# SparkFun_ESP8266_Thing.net
KiCad netlist of a schematic drawn in EAGLE
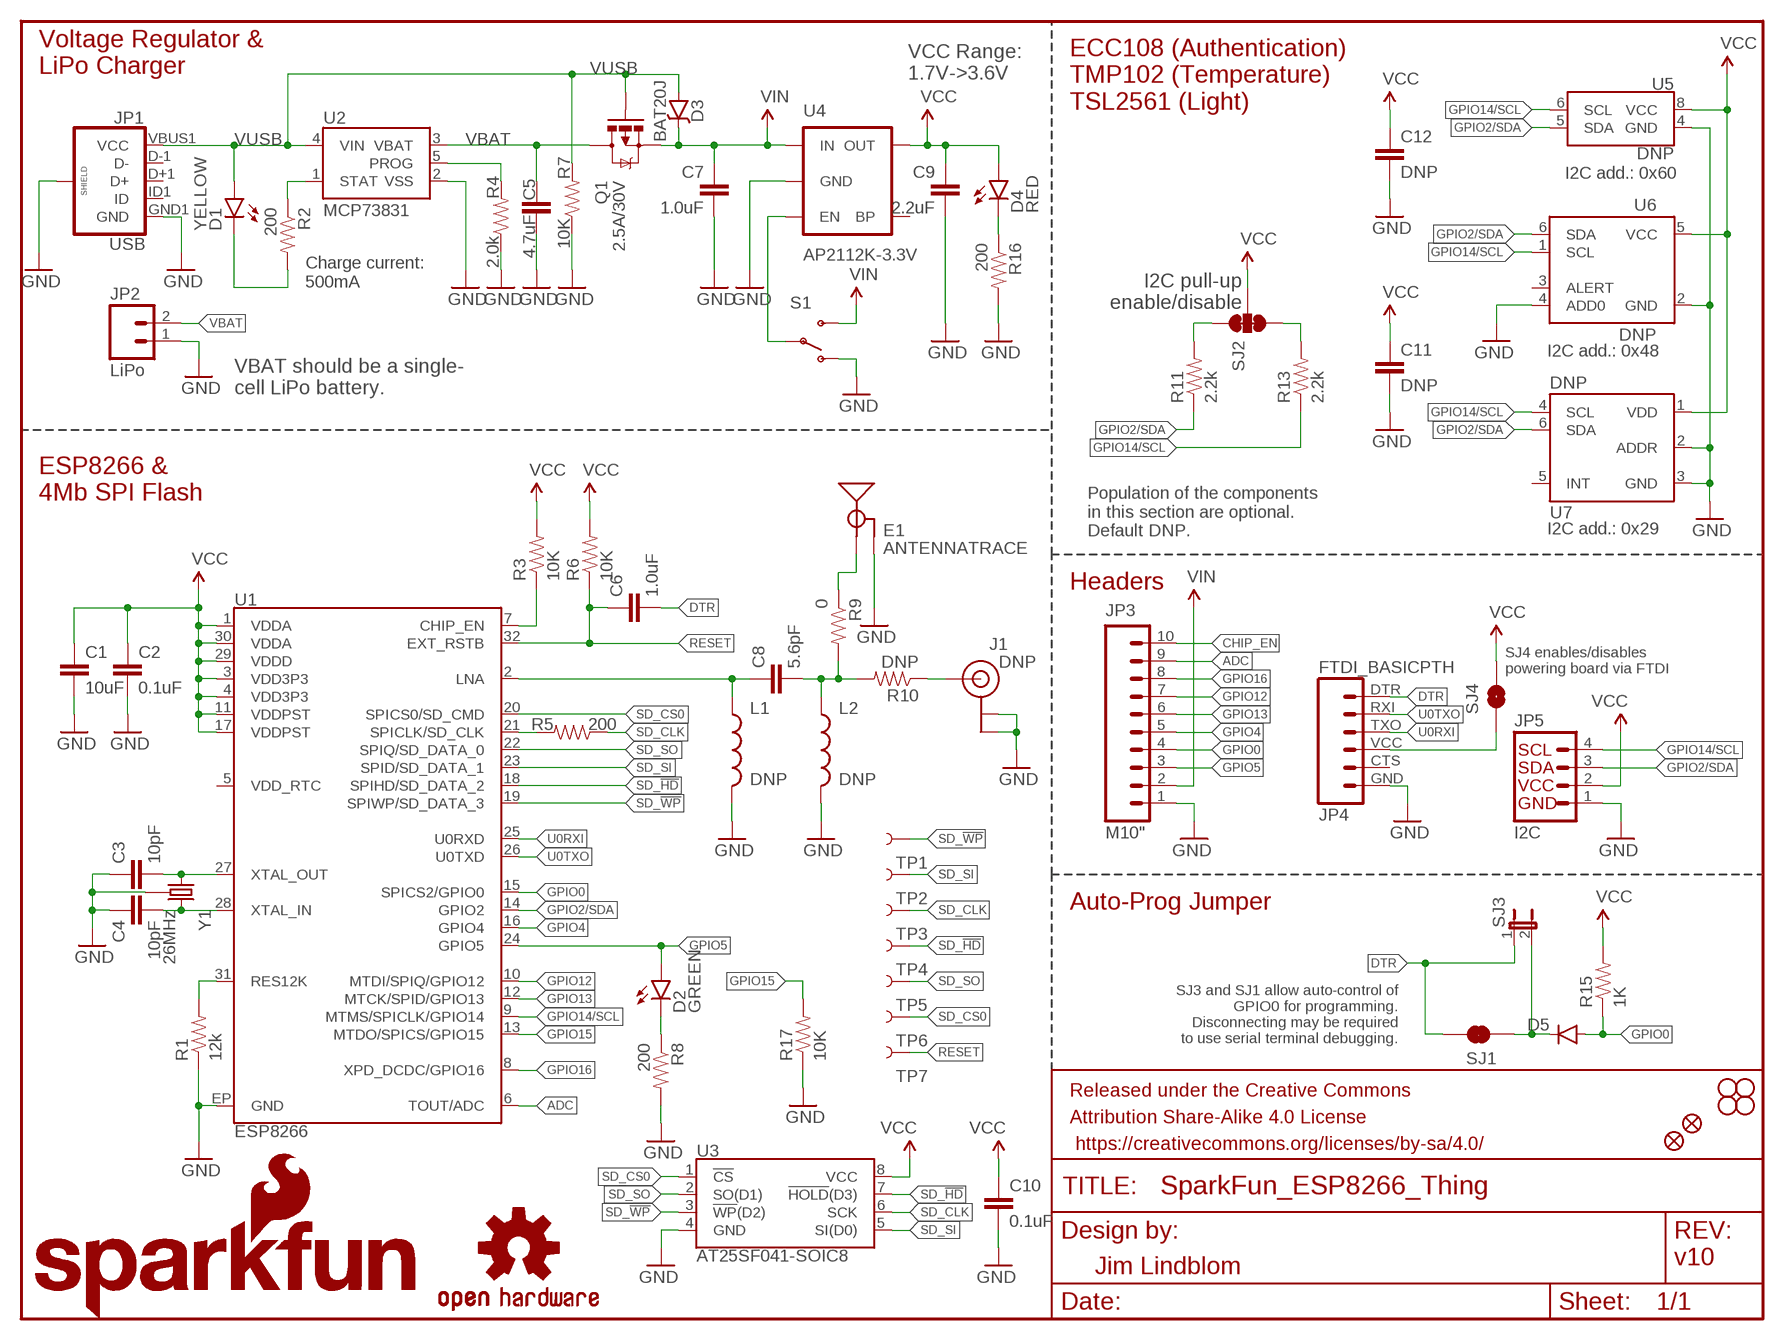
[diagram p0: schematic, sheet 1]

(export (version "E")
  (design (tool "Eeschema 10.0.6"))
  (components
    (comp (ref "C1")
      (value "10uF")
      (footprint "eagle-import:0603-CAP")
      (libsource (lib "eagle-import") (part "10UF-6.3V-20%(0603)"))
    )
    (comp (ref "C2")
      (value "0.1uF")
      (footprint "eagle-import:0603-CAP")
      (libsource (lib "eagle-import") (part "0.1UF-25V(+80/-20%)(0603)"))
    )
    (comp (ref "C3")
      (value "10pF")
      (footprint "eagle-import:0603-CAP")
      (libsource (lib "eagle-import") (part "10PF-50V-5%(0603)"))
    )
    (comp (ref "C4")
      (value "10pF")
      (footprint "eagle-import:0603-CAP")
      (libsource (lib "eagle-import") (part "10PF-50V-5%(0603)"))
    )
    (comp (ref "C5")
      (value "4.7uF")
      (footprint "eagle-import:0603-CAP")
      (libsource (lib "eagle-import") (part "4.7UF-6.3V-10%(0603)0603"))
    )
    (comp (ref "C6")
      (value "1.0uF")
      (footprint "eagle-import:0603-CAP")
      (libsource (lib "eagle-import") (part "1.0UF-16V-10%(0603)"))
    )
    (comp (ref "C7")
      (value "1.0uF")
      (footprint "eagle-import:0805")
      (libsource (lib "eagle-import") (part "1.0UF-25V-+80/-20(0805)"))
    )
    (comp (ref "C8")
      (value "5.6pF")
      (footprint "eagle-import:0603-CAP")
      (libsource (lib "eagle-import") (part "CAP0603-CAP"))
    )
    (comp (ref "C9")
      (value "2.2uF")
      (footprint "eagle-import:0603-CAP")
      (libsource (lib "eagle-import") (part "2.2UF-10V-20%(0603)"))
    )
    (comp (ref "C10")
      (value "0.1uF")
      (footprint "eagle-import:0603-CAP")
      (libsource (lib "eagle-import") (part "0.1UF-25V(+80/-20%)(0603)"))
    )
    (comp (ref "C11")
      (value "DNP")
      (footprint "eagle-import:0603-CAP")
      (libsource (lib "eagle-import") (part "0.1UF-25V(+80/-20%)(0603)"))
    )
    (comp (ref "C12")
      (value "DNP")
      (footprint "eagle-import:0603-CAP")
      (libsource (lib "eagle-import") (part "0.1UF-25V(+80/-20%)(0603)"))
    )
    (comp (ref "D1")
      (value "YELLOW")
      (footprint "eagle-import:LED-0603")
      (libsource (lib "eagle-import") (part "LED-YELLOW0603"))
    )
    (comp (ref "D2")
      (value "GREEN")
      (footprint "eagle-import:LED-0603")
      (libsource (lib "eagle-import") (part "LED-GREEN0603"))
    )
    (comp (ref "D3")
      (value "BAT20J")
      (footprint "eagle-import:SOD-323")
      (libsource (lib "eagle-import") (part "DIODE-SCHOTTKY-BAT20J"))
    )
    (comp (ref "D4")
      (value "RED")
      (footprint "eagle-import:LED-0603")
      (libsource (lib "eagle-import") (part "LED-RED0603"))
    )
    (comp (ref "D5")
      (value "DIODEBAS16")
      (footprint "eagle-import:SOD-323")
      (libsource (lib "eagle-import") (part "DIODEBAS16"))
    )
    (comp (ref "E1")
      (value "ANTENNATRACE")
      (footprint "eagle-import:TRACE_ANTENNA_2.4GHZ_25.7MM")
      (libsource (lib "eagle-import") (part "ANTENNATRACE"))
    )
    (comp (ref "FID1")
      (value "FIDUCIAL1X2")
      (footprint "eagle-import:FIDUCIAL-1X2")
      (libsource (lib "eagle-import") (part "FIDUCIAL1X2"))
    )
    (comp (ref "FID2")
      (value "FIDUCIAL1X2")
      (footprint "eagle-import:FIDUCIAL-1X2")
      (libsource (lib "eagle-import") (part "FIDUCIAL1X2"))
    )
    (comp (ref "FRAME1")
      (value "FRAME-LETTER")
      (footprint "eagle-import:CREATIVE_COMMONS")
      (libsource (lib "eagle-import") (part "FRAME-LETTER"))
    )
    (comp (ref "J1")
      (value "DNP")
      (footprint "eagle-import:U.FL")
      (libsource (lib "eagle-import") (part "U.FL"))
    )
    (comp (ref "JP1")
      (value "USB")
      (footprint "eagle-import:USB-B-MICRO-SMD_V03")
      (libsource (lib "eagle-import") (part "USB_MICROB_PLUGCONN-11752"))
    )
    (comp (ref "JP2")
      (value "LiPo")
      (footprint "eagle-import:JST-2-PTH")
      (libsource (lib "eagle-import") (part "M02JST-PTH-2"))
    )
    (comp (ref "JP3")
      (value "M10\"")
      (footprint "eagle-import:1X10")
      (libsource (lib "eagle-import") (part "M10{dblquote}"))
    )
    (comp (ref "JP4")
      (value "FTDI_BASICPTH")
      (footprint "eagle-import:FTDI_BASIC")
      (libsource (lib "eagle-import") (part "FTDI_BASICPTH"))
    )
    (comp (ref "JP5")
      (value "I2C")
      (footprint "eagle-import:1X04")
      (libsource (lib "eagle-import") (part "I2C_STANDARD"))
    )
    (comp (ref "L1")
      (value "DNP")
      (footprint "eagle-import:0603")
      (libsource (lib "eagle-import") (part "INDUCTOR0603"))
    )
    (comp (ref "L2")
      (value "DNP")
      (footprint "eagle-import:0603")
      (libsource (lib "eagle-import") (part "INDUCTOR0603"))
    )
    (comp (ref "LOGO1")
      (value "SFE_LOGO_NAME.2_INCH")
      (footprint "eagle-import:SFE_LOGO_NAME_.2")
      (libsource (lib "eagle-import") (part "SFE_LOGO_NAME.2_INCH"))
    )
    (comp (ref "LOGO3")
      (value "SFE_LOGO_FLAME.1_INCH")
      (footprint "eagle-import:SFE_LOGO_FLAME_.1")
      (libsource (lib "eagle-import") (part "SFE_LOGO_FLAME.1_INCH"))
    )
    (comp (ref "LOGO4")
      (value "OSHW-LOGOS")
      (footprint "eagle-import:OSHW-LOGO-S")
      (libsource (lib "eagle-import") (part "OSHW-LOGOS"))
    )
    (comp (ref "Q1")
      (value "2.5A/30V")
      (footprint "eagle-import:SOT23-3")
      (libsource (lib "eagle-import") (part "MOSFET-PCHANNELDMG2307L"))
    )
    (comp (ref "R1")
      (value "12k")
      (footprint "eagle-import:0603-RES")
      (libsource (lib "eagle-import") (part "12KOHM-1/10W-1%(0603)"))
    )
    (comp (ref "R2")
      (value "200")
      (footprint "eagle-import:0603-RES")
      (libsource (lib "eagle-import") (part "200OHM1/10W1%(0603)"))
    )
    (comp (ref "R3")
      (value "10K")
      (footprint "eagle-import:0603-RES")
      (libsource (lib "eagle-import") (part "10KOHM1/10W1%(0603)0603"))
    )
    (comp (ref "R4")
      (value "2.0k")
      (footprint "eagle-import:0603-RES")
      (libsource (lib "eagle-import") (part "2.0KOHM1/10W5%(0603)"))
    )
    (comp (ref "R5")
      (value "200")
      (footprint "eagle-import:0603-RES")
      (libsource (lib "eagle-import") (part "200OHM1/10W1%(0603)"))
    )
    (comp (ref "R6")
      (value "10K")
      (footprint "eagle-import:0603-RES")
      (libsource (lib "eagle-import") (part "10KOHM1/10W1%(0603)0603"))
    )
    (comp (ref "R7")
      (value "10K")
      (footprint "eagle-import:0603-RES")
      (libsource (lib "eagle-import") (part "10KOHM1/10W1%(0603)0603"))
    )
    (comp (ref "R8")
      (value "200")
      (footprint "eagle-import:0603-RES")
      (libsource (lib "eagle-import") (part "200OHM1/10W1%(0603)"))
    )
    (comp (ref "R9")
      (value "0")
      (footprint "eagle-import:0603")
      (libsource (lib "eagle-import") (part "0OHM1/10W5%(0603)"))
    )
    (comp (ref "R10")
      (value "DNP")
      (footprint "eagle-import:0603-RES")
      (libsource (lib "eagle-import") (part "RESISTOR0603-RES"))
    )
    (comp (ref "R11")
      (value "2.2k")
      (footprint "eagle-import:0603-RES")
      (libsource (lib "eagle-import") (part "2.2KOHM1/10W1%(0603)"))
    )
    (comp (ref "R13")
      (value "2.2k")
      (footprint "eagle-import:0603-RES")
      (libsource (lib "eagle-import") (part "2.2KOHM1/10W1%(0603)"))
    )
    (comp (ref "R15")
      (value "1K")
      (footprint "eagle-import:0603-RES")
      (libsource (lib "eagle-import") (part "1KOHM1/10W1%(0603)"))
    )
    (comp (ref "R16")
      (value "200")
      (footprint "eagle-import:0603-RES")
      (libsource (lib "eagle-import") (part "200OHM1/10W1%(0603)"))
    )
    (comp (ref "R17")
      (value "10K")
      (footprint "eagle-import:0603-RES")
      (libsource (lib "eagle-import") (part "10KOHM1/10W1%(0603)0603"))
    )
    (comp (ref "S1")
      (value "SWITCH-SPDT-SMD-A")
      (footprint "eagle-import:SWITCH-SPST-SMD-A")
      (libsource (lib "eagle-import") (part "SWITCH-SPDT-SMD-A"))
    )
    (comp (ref "SJ1")
      (value "JUMPER-PAD-2-NC_BY_TRACE")
      (footprint "eagle-import:PAD-JUMPER-2-NC_BY_TRACE_YES_SILK")
      (libsource (lib "eagle-import") (part "JUMPER-PAD-2-NC_BY_TRACE"))
    )
    (comp (ref "SJ2")
      (value "JUMPER-PAD-3-NC_BY_TRACE")
      (footprint "eagle-import:PAD-JUMPER-3-3OF3_NC_BY_TRACE_YES_SILK_FULL_BOX")
      (libsource (lib "eagle-import") (part "JUMPER-PAD-3-NC_BY_TRACE"))
    )
    (comp (ref "SJ3")
      (value "JUMPER-PTH-2-NC")
      (footprint "eagle-import:PTH-JUMPER-NC_BOTTOM_NO_SILK")
      (libsource (lib "eagle-import") (part "JUMPER-PTH-2-NC"))
    )
    (comp (ref "SJ4")
      (value "JUMPER-PAD-2-NOYES_SILK")
      (footprint "eagle-import:PAD-JUMPER-2-NO_YES_SILK")
      (libsource (lib "eagle-import") (part "JUMPER-PAD-2-NOYES_SILK"))
    )
    (comp (ref "STANDOFF1")
      (value "STAND-OFF")
      (footprint "eagle-import:STAND-OFF")
      (libsource (lib "eagle-import") (part "STAND-OFF"))
    )
    (comp (ref "STANDOFF2")
      (value "STAND-OFF")
      (footprint "eagle-import:STAND-OFF")
      (libsource (lib "eagle-import") (part "STAND-OFF"))
    )
    (comp (ref "STANDOFF3")
      (value "STAND-OFF")
      (footprint "eagle-import:STAND-OFF")
      (libsource (lib "eagle-import") (part "STAND-OFF"))
    )
    (comp (ref "STANDOFF4")
      (value "STAND-OFF")
      (footprint "eagle-import:STAND-OFF")
      (libsource (lib "eagle-import") (part "STAND-OFF"))
    )
    (comp (ref "TP1")
      (value "TEST-POINT3X5")
      (footprint "eagle-import:PAD.03X.05")
      (libsource (lib "eagle-import") (part "TEST-POINT3X5"))
    )
    (comp (ref "TP2")
      (value "TEST-POINT3X5")
      (footprint "eagle-import:PAD.03X.05")
      (libsource (lib "eagle-import") (part "TEST-POINT3X5"))
    )
    (comp (ref "TP3")
      (value "TEST-POINT3X5")
      (footprint "eagle-import:PAD.03X.05")
      (libsource (lib "eagle-import") (part "TEST-POINT3X5"))
    )
    (comp (ref "TP4")
      (value "TEST-POINT3X5")
      (footprint "eagle-import:PAD.03X.05")
      (libsource (lib "eagle-import") (part "TEST-POINT3X5"))
    )
    (comp (ref "TP5")
      (value "TEST-POINT3X5")
      (footprint "eagle-import:PAD.03X.05")
      (libsource (lib "eagle-import") (part "TEST-POINT3X5"))
    )
    (comp (ref "TP6")
      (value "TEST-POINT3X5")
      (footprint "eagle-import:PAD.03X.05")
      (libsource (lib "eagle-import") (part "TEST-POINT3X5"))
    )
    (comp (ref "TP7")
      (value "TEST-POINT3X5")
      (footprint "eagle-import:PAD.03X.05")
      (libsource (lib "eagle-import") (part "TEST-POINT3X5"))
    )
    (comp (ref "U1")
      (value "ESP8266")
      (footprint "eagle-import:QFN32")
      (libsource (lib "eagle-import") (part "ESP8266"))
    )
    (comp (ref "U2")
      (value "MCP73831")
      (footprint "eagle-import:SOT23-5")
      (libsource (lib "eagle-import") (part "MCP73831"))
    )
    (comp (ref "U3")
      (value "AT25SF041-SOIC8")
      (footprint "eagle-import:SO08")
      (libsource (lib "eagle-import") (part "AT25SF041-SOIC8"))
    )
    (comp (ref "U4")
      (value "AP2112K-3.3V")
      (footprint "eagle-import:SOT23-5")
      (libsource (lib "eagle-import") (part "V_REG_LDOSMD"))
    )
    (comp (ref "U5")
      (value "DNP")
      (footprint "eagle-import:UDFN8")
      (libsource (lib "eagle-import") (part "ATECC108-MAHDA"))
    )
    (comp (ref "U6")
      (value "DNP")
      (footprint "eagle-import:SOT563-2")
      (libsource (lib "eagle-import") (part "TMP1021{colon}1"))
    )
    (comp (ref "U7")
      (value "DNP")
      (footprint "eagle-import:FN-6")
      (libsource (lib "eagle-import") (part "TSL2561FN"))
    )
    (comp (ref "Y1")
      (value "26MHz")
      (footprint "eagle-import:CRYSTAL-SMD-3.2X2.5")
      (libsource (lib "eagle-import") (part "CRYSTAL-GROUNDED3.2X2.5"))
    )
  )
  (nets
    (net (code "1") (name "/SD_~{HD}") (class "Default")
      (node (ref "TP4") (pin "P$1") (pinfunction "1_P$1") (pintype "bidirectional"))
      (node (ref "U1") (pin "18") (pinfunction "SPIHD/SD_DATA_2_18") (pintype "bidirectional"))
      (node (ref "U3") (pin "7") (pinfunction "~{HOLD}(D3)_7") (pintype "bidirectional"))
    )
    (net (code "2") (name "/SD_~{WP}") (class "Default")
      (node (ref "TP1") (pin "P$1") (pinfunction "1_P$1") (pintype "bidirectional"))
      (node (ref "U1") (pin "19") (pinfunction "SPIWP/SD_DATA_3_19") (pintype "bidirectional"))
      (node (ref "U3") (pin "3") (pinfunction "~{WP}(D2)_3") (pintype "bidirectional"))
    )
    (net (code "3") (name "/VUSB") (class "Default")
      (node (ref "D1") (pin "A") (pinfunction "A_A") (pintype "passive"))
      (node (ref "D3") (pin "A") (pinfunction "A_A") (pintype "passive"))
      (node (ref "JP1") (pin "VBUS1") (pinfunction "VCC_VBUS1") (pintype "bidirectional"))
      (node (ref "Q1") (pin "1") (pinfunction "G_1") (pintype "passive"))
      (node (ref "R7") (pin "2") (pinfunction "2_2") (pintype "passive"))
      (node (ref "U2") (pin "4") (pinfunction "VIN_4") (pintype "power_in"))
    )
    (net (code "4") (name "ADC") (class "Default")
      (node (ref "JP3") (pin "9") (pinfunction "9_9") (pintype "passive"))
      (node (ref "U1") (pin "6") (pinfunction "TOUT/ADC_6") (pintype "bidirectional"))
    )
    (net (code "5") (name "CHIP_EN") (class "Default")
      (node (ref "JP3") (pin "10") (pinfunction "10_10") (pintype "passive"))
      (node (ref "R3") (pin "1") (pinfunction "1_1") (pintype "passive"))
      (node (ref "U1") (pin "7") (pinfunction "CHIP_EN_7") (pintype "bidirectional"))
    )
    (net (code "6") (name "DTR") (class "Default")
      (node (ref "C6") (pin "2") (pinfunction "2_2") (pintype "passive"))
      (node (ref "JP4") (pin "DTR") (pinfunction "1_DTR") (pintype "passive"))
      (node (ref "SJ1") (pin "2") (pinfunction "2_2") (pintype "passive"))
      (node (ref "SJ3") (pin "1") (pinfunction "1_1") (pintype "passive"))
    )
    (net (code "7") (name "GND") (class "Default")
      (node (ref "C1") (pin "2") (pinfunction "2_2") (pintype "passive"))
      (node (ref "C10") (pin "2") (pinfunction "2_2") (pintype "passive"))
      (node (ref "C11") (pin "2") (pinfunction "2_2") (pintype "passive"))
      (node (ref "C12") (pin "2") (pinfunction "2_2") (pintype "passive"))
      (node (ref "C2") (pin "2") (pinfunction "2_2") (pintype "passive"))
      (node (ref "C3") (pin "1") (pinfunction "1_1") (pintype "passive"))
      (node (ref "C4") (pin "1") (pinfunction "1_1") (pintype "passive"))
      (node (ref "C5") (pin "2") (pinfunction "2_2") (pintype "passive"))
      (node (ref "C7") (pin "2") (pinfunction "2_2") (pintype "passive"))
      (node (ref "C9") (pin "2") (pinfunction "2_2") (pintype "passive"))
      (node (ref "E1") (pin "GND") (pinfunction "GND_GND") (pintype "bidirectional"))
      (node (ref "E1") (pin "GND2") (pinfunction "GND_GND2") (pintype "bidirectional"))
      (node (ref "J1") (pin "P$1") (pinfunction "GND_P$1") (pintype "bidirectional"))
      (node (ref "J1") (pin "P$2") (pinfunction "GND_P$2") (pintype "bidirectional"))
      (node (ref "JP1") (pin "GND1") (pinfunction "GND_GND1") (pintype "bidirectional"))
      (node (ref "JP1") (pin "SHIELD1") (pinfunction "SHIELD_SHIELD1") (pintype "bidirectional"))
      (node (ref "JP1") (pin "SHIELD2") (pinfunction "SHIELD_SHIELD2") (pintype "bidirectional"))
      (node (ref "JP1") (pin "SHIELD3") (pinfunction "SHIELD_SHIELD3") (pintype "bidirectional"))
      (node (ref "JP2") (pin "1") (pinfunction "1_1") (pintype "passive"))
      (node (ref "JP3") (pin "1") (pinfunction "1_1") (pintype "passive"))
      (node (ref "JP4") (pin "GND") (pinfunction "6_GND") (pintype "passive"))
      (node (ref "JP5") (pin "1") (pinfunction "1_1") (pintype "passive"))
      (node (ref "L1") (pin "2") (pinfunction "2_2") (pintype "passive"))
      (node (ref "L2") (pin "2") (pinfunction "2_2") (pintype "passive"))
      (node (ref "R1") (pin "1") (pinfunction "1_1") (pintype "passive"))
      (node (ref "R16") (pin "2") (pinfunction "2_2") (pintype "passive"))
      (node (ref "R17") (pin "1") (pinfunction "1_1") (pintype "passive"))
      (node (ref "R4") (pin "1") (pinfunction "1_1") (pintype "passive"))
      (node (ref "R7") (pin "1") (pinfunction "1_1") (pintype "passive"))
      (node (ref "R8") (pin "2") (pinfunction "2_2") (pintype "passive"))
      (node (ref "S1") (pin "1") (pinfunction "O_1") (pintype "passive"))
      (node (ref "U1") (pin "EP") (pinfunction "GND_EP") (pintype "bidirectional"))
      (node (ref "U2") (pin "2") (pinfunction "VSS_2") (pintype "power_in"))
      (node (ref "U3") (pin "4") (pinfunction "GND_4") (pintype "bidirectional"))
      (node (ref "U4") (pin "2") (pinfunction "GND_2") (pintype "input"))
      (node (ref "U5") (pin "4") (pinfunction "GND_4") (pintype "bidirectional"))
      (node (ref "U6") (pin "2") (pinfunction "GND_2") (pintype "bidirectional"))
      (node (ref "U6") (pin "4") (pinfunction "ADD0_4") (pintype "bidirectional"))
      (node (ref "U7") (pin "2") (pinfunction "ADDR_2") (pintype "input"))
      (node (ref "U7") (pin "3") (pinfunction "GND_3") (pintype "power_in"))
      (node (ref "Y1") (pin "2") (pinfunction "GND_2") (pintype "passive"))
      (node (ref "Y1") (pin "4") (pinfunction "GND_4") (pintype "passive"))
    )
    (net (code "8") (name "GPIO0") (class "Default")
      (node (ref "D5") (pin "A") (pinfunction "A_A") (pintype "passive"))
      (node (ref "JP3") (pin "4") (pinfunction "4_4") (pintype "passive"))
      (node (ref "R15") (pin "1") (pinfunction "1_1") (pintype "passive"))
      (node (ref "U1") (pin "15") (pinfunction "SPICS2/GPIO0_15") (pintype "bidirectional"))
    )
    (net (code "9") (name "GPIO2{slash}SDA") (class "Default")
      (node (ref "JP5") (pin "3") (pinfunction "3_3") (pintype "passive"))
      (node (ref "R11") (pin "1") (pinfunction "1_1") (pintype "passive"))
      (node (ref "U1") (pin "14") (pinfunction "GPIO2_14") (pintype "bidirectional"))
      (node (ref "U5") (pin "5") (pinfunction "SDA_5") (pintype "bidirectional"))
      (node (ref "U6") (pin "6") (pinfunction "SDA_6") (pintype "bidirectional"))
      (node (ref "U7") (pin "6") (pinfunction "SDA_6") (pintype "bidirectional"))
    )
    (net (code "10") (name "GPIO4") (class "Default")
      (node (ref "JP3") (pin "5") (pinfunction "5_5") (pintype "passive"))
      (node (ref "U1") (pin "16") (pinfunction "GPIO4_16") (pintype "bidirectional"))
    )
    (net (code "11") (name "GPIO5") (class "Default")
      (node (ref "D2") (pin "A") (pinfunction "A_A") (pintype "passive"))
      (node (ref "JP3") (pin "3") (pinfunction "3_3") (pintype "passive"))
      (node (ref "U1") (pin "24") (pinfunction "GPIO5_24") (pintype "bidirectional"))
    )
    (net (code "12") (name "GPIO12") (class "Default")
      (node (ref "JP3") (pin "7") (pinfunction "7_7") (pintype "passive"))
      (node (ref "U1") (pin "10") (pinfunction "MTDI/SPIQ/GPIO12_10") (pintype "bidirectional"))
    )
    (net (code "13") (name "GPIO13") (class "Default")
      (node (ref "JP3") (pin "6") (pinfunction "6_6") (pintype "passive"))
      (node (ref "U1") (pin "12") (pinfunction "MTCK/SPID/GPIO13_12") (pintype "bidirectional"))
    )
    (net (code "14") (name "GPIO14{slash}SCL") (class "Default")
      (node (ref "JP5") (pin "4") (pinfunction "4_4") (pintype "passive"))
      (node (ref "R13") (pin "1") (pinfunction "1_1") (pintype "passive"))
      (node (ref "U1") (pin "9") (pinfunction "MTMS/SPICLK/GPIO14_9") (pintype "bidirectional"))
      (node (ref "U5") (pin "6") (pinfunction "SCL_6") (pintype "bidirectional"))
      (node (ref "U6") (pin "1") (pinfunction "SCL_1") (pintype "bidirectional"))
      (node (ref "U7") (pin "4") (pinfunction "SCL_4") (pintype "input"))
    )
    (net (code "15") (name "GPIO15") (class "Default")
      (node (ref "R17") (pin "2") (pinfunction "2_2") (pintype "passive"))
      (node (ref "U1") (pin "13") (pinfunction "MTDO/SPICS/GPIO15_13") (pintype "bidirectional"))
    )
    (net (code "16") (name "GPIO16") (class "Default")
      (node (ref "JP3") (pin "8") (pinfunction "8_8") (pintype "passive"))
      (node (ref "U1") (pin "8") (pinfunction "XPD_DCDC/GPIO16_8") (pintype "bidirectional"))
    )
    (net (code "17") (name "Net-(C8-Pad2)") (class "Default")
      (node (ref "C8") (pin "2") (pinfunction "2_2") (pintype "passive"))
      (node (ref "L2") (pin "1") (pinfunction "1_1") (pintype "passive"))
      (node (ref "R10") (pin "2") (pinfunction "2_2") (pintype "passive"))
      (node (ref "R9") (pin "2") (pinfunction "2_2") (pintype "passive"))
    )
    (net (code "18") (name "Net-(D1-PadC)") (class "Default")
      (node (ref "D1") (pin "C") (pinfunction "C_C") (pintype "passive"))
      (node (ref "R2") (pin "2") (pinfunction "2_2") (pintype "passive"))
    )
    (net (code "19") (name "Net-(D2-PadC)") (class "Default")
      (node (ref "D2") (pin "C") (pinfunction "C_C") (pintype "passive"))
      (node (ref "R8") (pin "1") (pinfunction "1_1") (pintype "passive"))
    )
    (net (code "20") (name "Net-(D4-PadC)") (class "Default")
      (node (ref "D4") (pin "C") (pinfunction "C_C") (pintype "passive"))
      (node (ref "R16") (pin "1") (pinfunction "1_1") (pintype "passive"))
    )
    (net (code "21") (name "Net-(D5-PadC)") (class "Default")
      (node (ref "D5") (pin "C") (pinfunction "C_C") (pintype "passive"))
      (node (ref "SJ1") (pin "1") (pinfunction "1_1") (pintype "passive"))
      (node (ref "SJ3") (pin "2") (pinfunction "2_2") (pintype "passive"))
    )
    (net (code "22") (name "Net-(E1-SIGNAL)") (class "Default")
      (node (ref "E1") (pin "ANT") (pinfunction "SIGNAL_ANT") (pintype "bidirectional"))
      (node (ref "R9") (pin "1") (pinfunction "1_1") (pintype "passive"))
    )
    (net (code "23") (name "Net-(J1-SIGNAL)") (class "Default")
      (node (ref "J1") (pin "P$3") (pinfunction "SIGNAL_P$3") (pintype "bidirectional"))
      (node (ref "R10") (pin "1") (pinfunction "1_1") (pintype "passive"))
    )
    (net (code "24") (name "Net-(JP4-4)") (class "Default")
      (node (ref "JP4") (pin "VCC") (pinfunction "4_VCC") (pintype "passive"))
      (node (ref "SJ4") (pin "1") (pinfunction "1_1") (pintype "passive"))
    )
    (net (code "25") (name "Net-(R11-Pad2)") (class "Default")
      (node (ref "R11") (pin "2") (pinfunction "2_2") (pintype "passive"))
      (node (ref "SJ2") (pin "1") (pinfunction "1_1") (pintype "passive"))
    )
    (net (code "26") (name "Net-(R13-Pad2)") (class "Default")
      (node (ref "R13") (pin "2") (pinfunction "2_2") (pintype "passive"))
      (node (ref "SJ2") (pin "3") (pinfunction "3_3") (pintype "passive"))
    )
    (net (code "27") (name "Net-(S1-P)") (class "Default")
      (node (ref "S1") (pin "2") (pinfunction "P_2") (pintype "passive"))
      (node (ref "U4") (pin "3") (pinfunction "EN_3") (pintype "input"))
    )
    (net (code "28") (name "Net-(U1-LNA)") (class "Default")
      (node (ref "C8") (pin "1") (pinfunction "1_1") (pintype "passive"))
      (node (ref "L1") (pin "1") (pinfunction "1_1") (pintype "passive"))
      (node (ref "U1") (pin "2") (pinfunction "LNA_2") (pintype "bidirectional"))
    )
    (net (code "29") (name "Net-(U1-RES12K)") (class "Default")
      (node (ref "R1") (pin "2") (pinfunction "2_2") (pintype "passive"))
      (node (ref "U1") (pin "31") (pinfunction "RES12K_31") (pintype "bidirectional"))
    )
    (net (code "30") (name "Net-(U1-SPICLK{slash}SD_CLK)") (class "Default")
      (node (ref "R5") (pin "2") (pinfunction "2_2") (pintype "passive"))
      (node (ref "U1") (pin "21") (pinfunction "SPICLK/SD_CLK_21") (pintype "bidirectional"))
    )
    (net (code "31") (name "Net-(U1-XTAL_IN)") (class "Default")
      (node (ref "C4") (pin "2") (pinfunction "2_2") (pintype "passive"))
      (node (ref "U1") (pin "28") (pinfunction "XTAL_IN_28") (pintype "bidirectional"))
      (node (ref "Y1") (pin "3") (pinfunction "2_3") (pintype "passive"))
    )
    (net (code "32") (name "Net-(U1-XTAL_OUT)") (class "Default")
      (node (ref "C3") (pin "2") (pinfunction "2_2") (pintype "passive"))
      (node (ref "U1") (pin "27") (pinfunction "XTAL_OUT_27") (pintype "bidirectional"))
      (node (ref "Y1") (pin "1") (pinfunction "1_1") (pintype "passive"))
    )
    (net (code "33") (name "Net-(U2-PROG)") (class "Default")
      (node (ref "R4") (pin "2") (pinfunction "2_2") (pintype "passive"))
      (node (ref "U2") (pin "5") (pinfunction "PROG_5") (pintype "input"))
    )
    (net (code "34") (name "Net-(U2-STAT)") (class "Default")
      (node (ref "R2") (pin "1") (pinfunction "1_1") (pintype "passive"))
      (node (ref "U2") (pin "1") (pinfunction "STAT_1") (pintype "output"))
    )
    (net (code "35") (name "RESET") (class "Default")
      (node (ref "C6") (pin "1") (pinfunction "1_1") (pintype "passive"))
      (node (ref "R6") (pin "1") (pinfunction "1_1") (pintype "passive"))
      (node (ref "TP7") (pin "P$1") (pinfunction "1_P$1") (pintype "bidirectional"))
      (node (ref "U1") (pin "32") (pinfunction "EXT_RSTB_32") (pintype "bidirectional"))
    )
    (net (code "36") (name "SD_CLK") (class "Default")
      (node (ref "R5") (pin "1") (pinfunction "1_1") (pintype "passive"))
      (node (ref "TP3") (pin "P$1") (pinfunction "1_P$1") (pintype "bidirectional"))
      (node (ref "U3") (pin "6") (pinfunction "SCK_6") (pintype "bidirectional"))
    )
    (net (code "37") (name "SD_CS0") (class "Default")
      (node (ref "TP6") (pin "P$1") (pinfunction "1_P$1") (pintype "bidirectional"))
      (node (ref "U1") (pin "20") (pinfunction "SPICS0/SD_CMD_20") (pintype "bidirectional"))
      (node (ref "U3") (pin "1") (pinfunction "~{CS}_1") (pintype "bidirectional"))
    )
    (net (code "38") (name "SD_SI") (class "Default")
      (node (ref "TP2") (pin "P$1") (pinfunction "1_P$1") (pintype "bidirectional"))
      (node (ref "U1") (pin "23") (pinfunction "SPID/SD_DATA_1_23") (pintype "bidirectional"))
      (node (ref "U3") (pin "5") (pinfunction "SI(D0)_5") (pintype "bidirectional"))
    )
    (net (code "39") (name "SD_SO") (class "Default")
      (node (ref "TP5") (pin "P$1") (pinfunction "1_P$1") (pintype "bidirectional"))
      (node (ref "U1") (pin "22") (pinfunction "SPIQ/SD_DATA_0_22") (pintype "bidirectional"))
      (node (ref "U3") (pin "2") (pinfunction "SO(D1)_2") (pintype "bidirectional"))
    )
    (net (code "40") (name "U0RXI") (class "Default")
      (node (ref "JP4") (pin "TXO") (pinfunction "3_TXO") (pintype "passive"))
      (node (ref "U1") (pin "25") (pinfunction "U0RXD_25") (pintype "bidirectional"))
    )
    (net (code "41") (name "U0TXO") (class "Default")
      (node (ref "JP4") (pin "RXI") (pinfunction "2_RXI") (pintype "passive"))
      (node (ref "U1") (pin "26") (pinfunction "U0TXD_26") (pintype "bidirectional"))
    )
    (net (code "42") (name "VBAT") (class "Default")
      (node (ref "C5") (pin "1") (pinfunction "1_1") (pintype "passive"))
      (node (ref "JP2") (pin "2") (pinfunction "2_2") (pintype "passive"))
      (node (ref "Q1") (pin "3") (pinfunction "D_3") (pintype "passive"))
      (node (ref "U2") (pin "3") (pinfunction "VBAT_3") (pintype "power_in"))
    )
    (net (code "43") (name "VCC") (class "Default")
      (node (ref "C1") (pin "1") (pinfunction "1_1") (pintype "passive"))
      (node (ref "C10") (pin "1") (pinfunction "1_1") (pintype "passive"))
      (node (ref "C11") (pin "1") (pinfunction "1_1") (pintype "passive"))
      (node (ref "C12") (pin "1") (pinfunction "1_1") (pintype "passive"))
      (node (ref "C2") (pin "1") (pinfunction "1_1") (pintype "passive"))
      (node (ref "C9") (pin "1") (pinfunction "1_1") (pintype "passive"))
      (node (ref "D4") (pin "A") (pinfunction "A_A") (pintype "passive"))
      (node (ref "JP5") (pin "2") (pinfunction "2_2") (pintype "passive"))
      (node (ref "R15") (pin "2") (pinfunction "2_2") (pintype "passive"))
      (node (ref "R3") (pin "2") (pinfunction "2_2") (pintype "passive"))
      (node (ref "R6") (pin "2") (pinfunction "2_2") (pintype "passive"))
      (node (ref "SJ2") (pin "2") (pinfunction "2_2") (pintype "passive"))
      (node (ref "SJ4") (pin "2") (pinfunction "2_2") (pintype "passive"))
      (node (ref "U1") (pin "1") (pinfunction "VDDA_1") (pintype "bidirectional"))
      (node (ref "U1") (pin "11") (pinfunction "VDDPST_11") (pintype "bidirectional"))
      (node (ref "U1") (pin "17") (pinfunction "VDDPST_17") (pintype "bidirectional"))
      (node (ref "U1") (pin "29") (pinfunction "VDDD_29") (pintype "bidirectional"))
      (node (ref "U1") (pin "3") (pinfunction "VDD3P3_3") (pintype "bidirectional"))
      (node (ref "U1") (pin "30") (pinfunction "VDDA_30") (pintype "bidirectional"))
      (node (ref "U1") (pin "4") (pinfunction "VDD3P3_4") (pintype "bidirectional"))
      (node (ref "U3") (pin "8") (pinfunction "VCC_8") (pintype "bidirectional"))
      (node (ref "U4") (pin "5") (pinfunction "OUT_5") (pintype "passive"))
      (node (ref "U5") (pin "8") (pinfunction "VCC_8") (pintype "bidirectional"))
      (node (ref "U6") (pin "5") (pinfunction "VCC_5") (pintype "bidirectional"))
      (node (ref "U7") (pin "1") (pinfunction "VDD_1") (pintype "power_in"))
    )
    (net (code "44") (name "VIN") (class "Default")
      (node (ref "C7") (pin "1") (pinfunction "1_1") (pintype "passive"))
      (node (ref "D3") (pin "C") (pinfunction "C_C") (pintype "passive"))
      (node (ref "JP3") (pin "2") (pinfunction "2_2") (pintype "passive"))
      (node (ref "Q1") (pin "2") (pinfunction "S_2") (pintype "passive"))
      (node (ref "S1") (pin "3") (pinfunction "S_3") (pintype "passive"))
      (node (ref "U4") (pin "1") (pinfunction "IN_1") (pintype "input"))
    )
    (net (code "45") (name "unconnected-(JP1-D+-PadD+1)") (class "Default")
      (node (ref "JP1") (pin "D+1") (pinfunction "D+_D+1") (pintype "bidirectional"))
    )
    (net (code "46") (name "unconnected-(JP1-D--PadD-1)") (class "Default")
      (node (ref "JP1") (pin "D-1") (pinfunction "D-_D-1") (pintype "bidirectional"))
    )
    (net (code "47") (name "unconnected-(JP1-ID-PadID1)") (class "Default")
      (node (ref "JP1") (pin "ID1") (pinfunction "ID_ID1") (pintype "bidirectional"))
    )
    (net (code "48") (name "unconnected-(JP4-5-PadCTS)") (class "Default")
      (node (ref "JP4") (pin "CTS") (pinfunction "5_CTS") (pintype "passive"))
    )
    (net (code "49") (name "unconnected-(U1-VDD_RTC-Pad5)") (class "Default")
      (node (ref "U1") (pin "5") (pinfunction "VDD_RTC_5") (pintype "bidirectional"))
    )
    (net (code "50") (name "unconnected-(U4-BP-Pad4)") (class "Default")
      (node (ref "U4") (pin "4") (pinfunction "BP_4") (pintype "input"))
    )
    (net (code "51") (name "unconnected-(U6-ALERT-Pad3)") (class "Default")
      (node (ref "U6") (pin "3") (pinfunction "ALERT_3") (pintype "bidirectional"))
    )
    (net (code "52") (name "unconnected-(U7-INT-Pad5)") (class "Default")
      (node (ref "U7") (pin "5") (pinfunction "INT_5") (pintype "output"))
    )
  )
)
